# MITAvionicsRevA.net
KiCad netlist of a schematic drawn in EAGLE
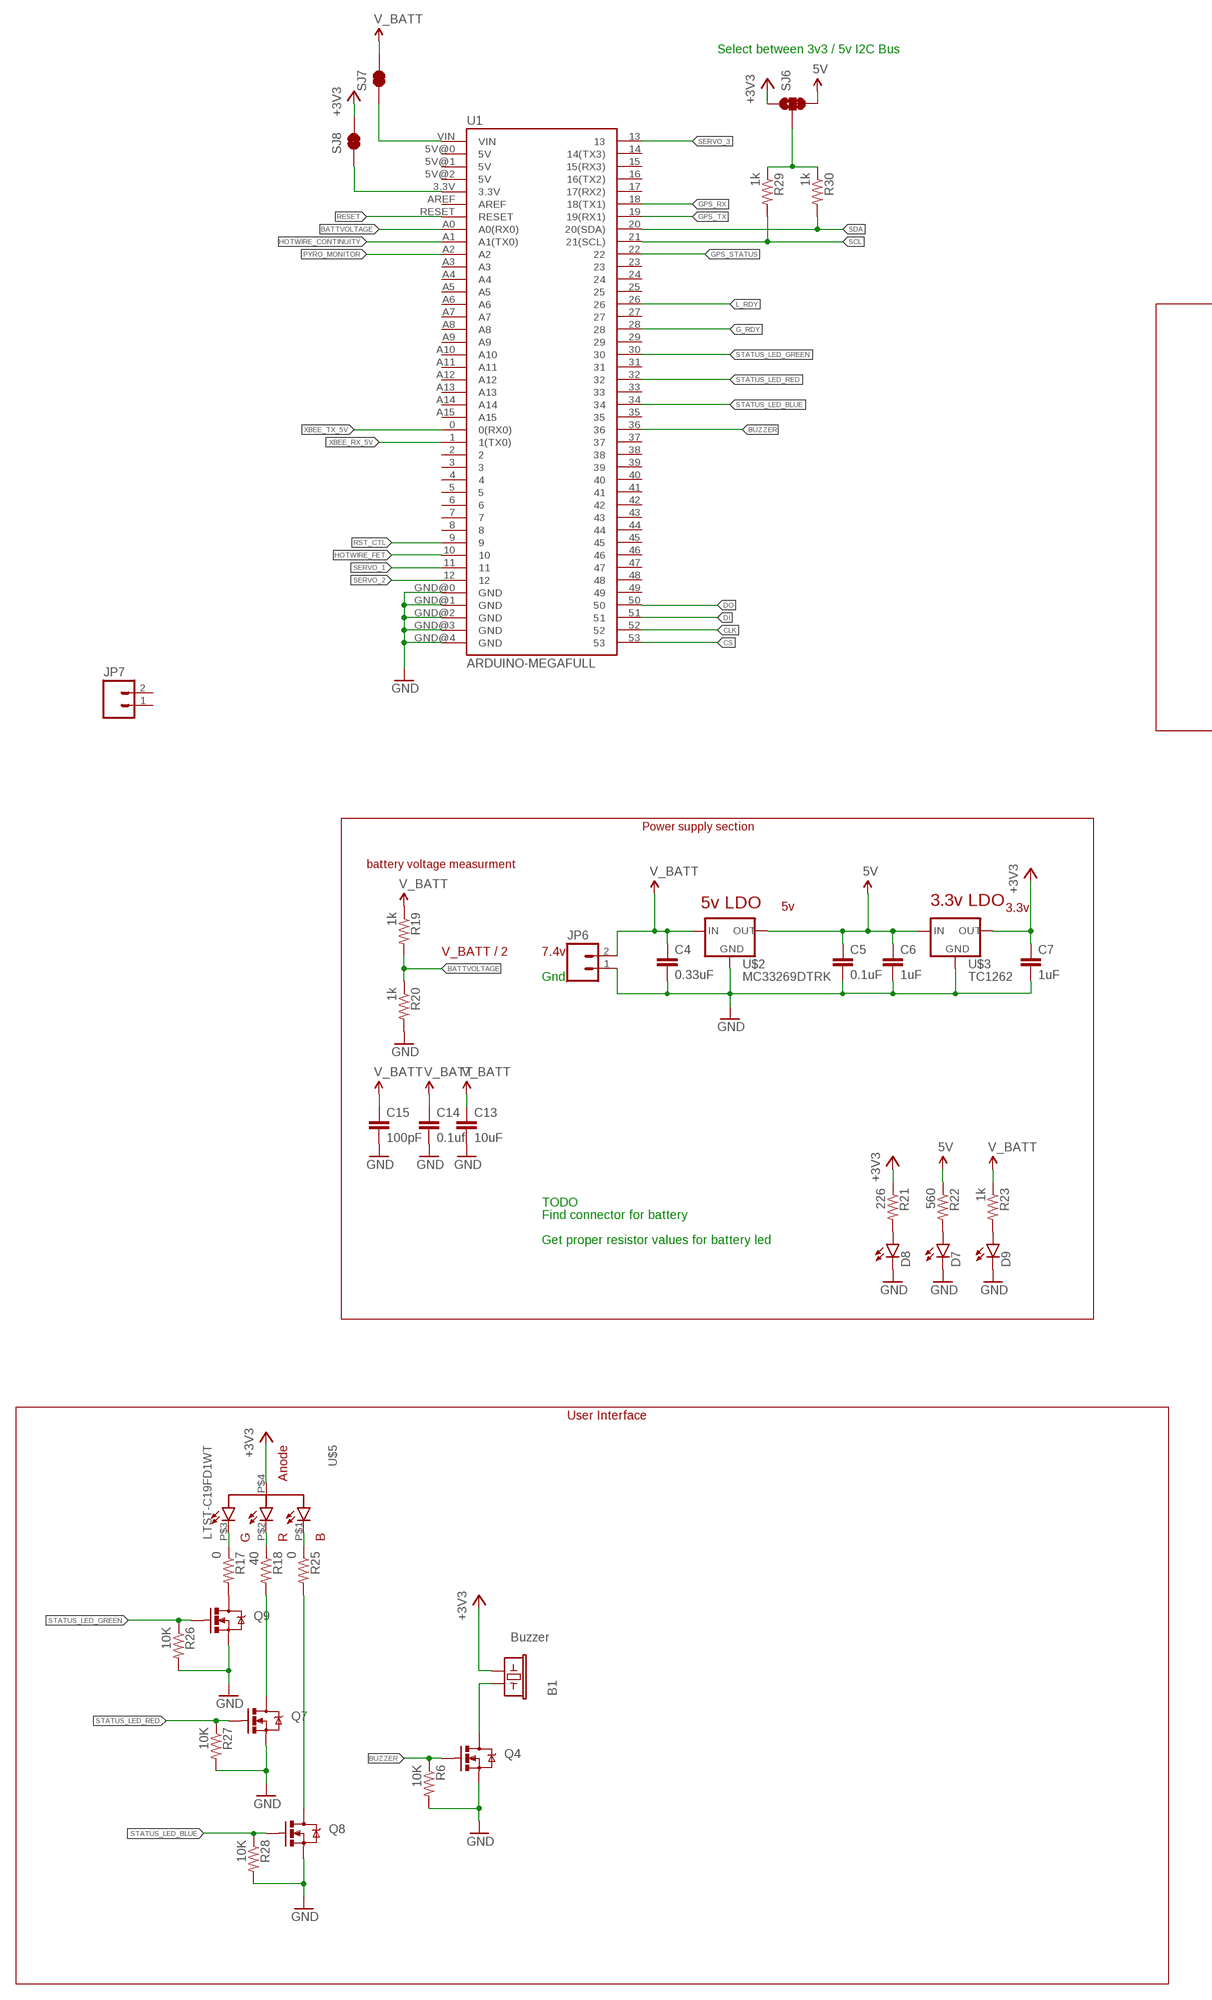
[diagram p0: schematic, sheet 1, part 1 of 2]
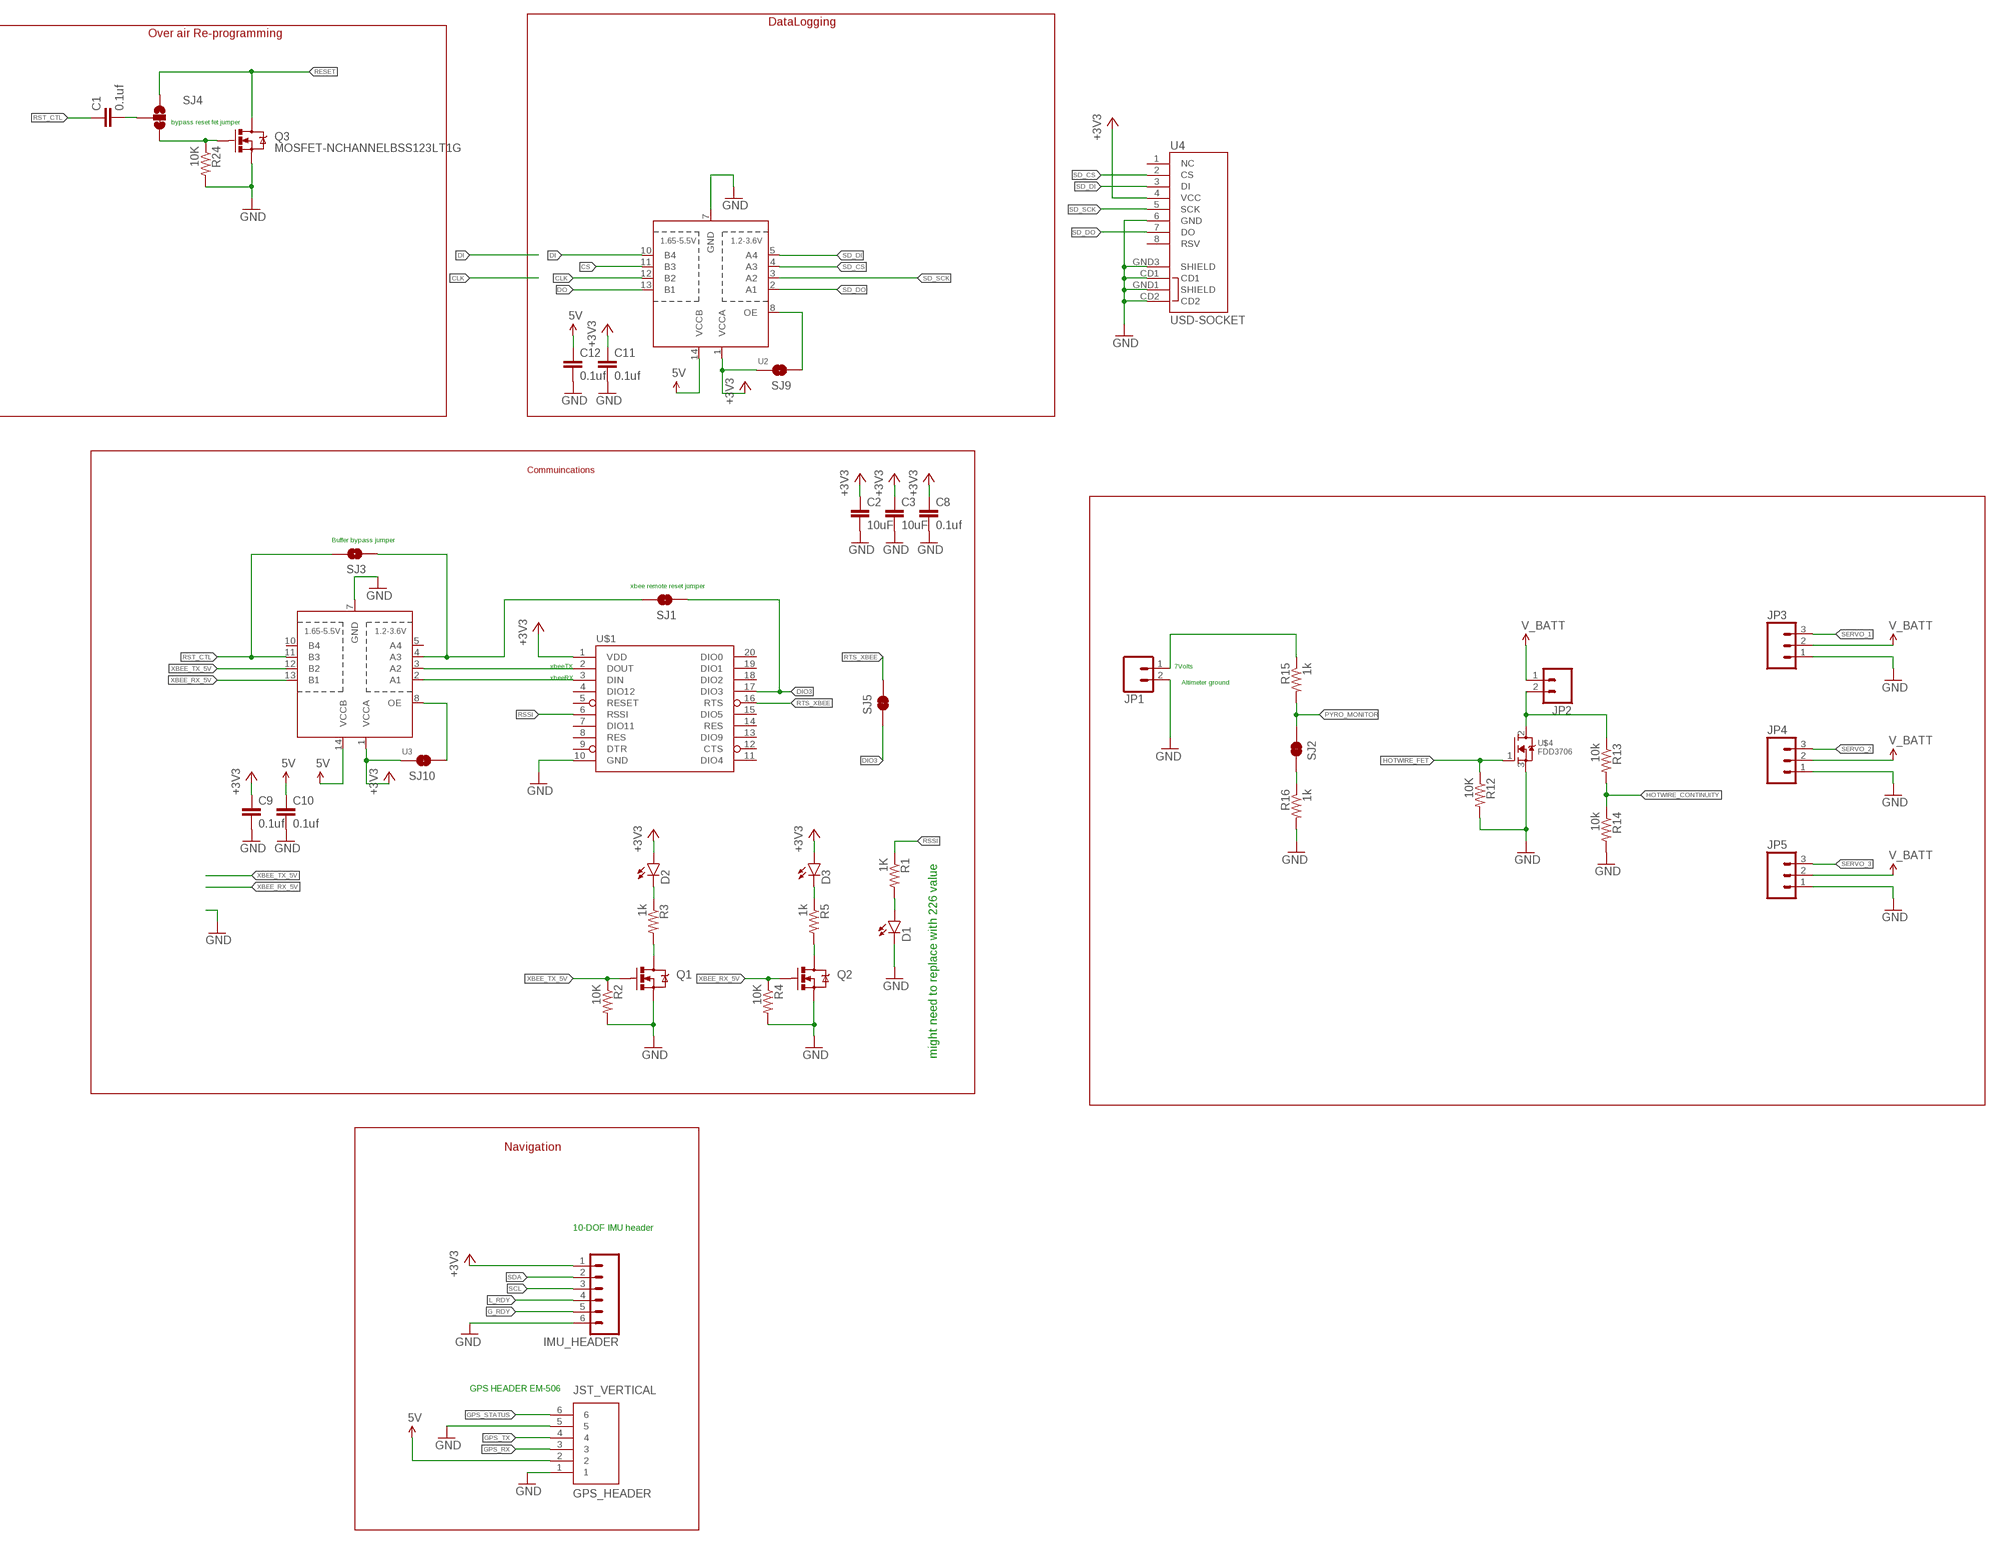
[diagram p1: schematic, sheet 1, part 2 of 2]

(export (version "E")
  (design (tool "Eeschema 10.0.6"))
  (components
    (comp (ref "B1")
      (value "Buzzer")
      (footprint "eagle-import:BUZZER-CCV")
      (libsource (lib "eagle-import") (part "BUZZERSMD2"))
    )
    (comp (ref "C1")
      (value "0.1uf")
      (footprint "eagle-import:0805")
      (libsource (lib "eagle-import") (part "CAP0805"))
    )
    (comp (ref "C2")
      (value "10uF")
      (footprint "eagle-import:0805")
      (libsource (lib "eagle-import") (part "CAP0805"))
    )
    (comp (ref "C3")
      (value "10uF")
      (footprint "eagle-import:0805")
      (libsource (lib "eagle-import") (part "CAP0805"))
    )
    (comp (ref "C4")
      (value "0.33uF")
      (footprint "eagle-import:0805")
      (libsource (lib "eagle-import") (part "CAP0805"))
    )
    (comp (ref "C5")
      (value "0.1uF")
      (footprint "eagle-import:0805")
      (libsource (lib "eagle-import") (part "CAP0805"))
    )
    (comp (ref "C6")
      (value "1uF")
      (footprint "eagle-import:0805")
      (libsource (lib "eagle-import") (part "CAP0805"))
    )
    (comp (ref "C7")
      (value "1uF")
      (footprint "eagle-import:0805")
      (libsource (lib "eagle-import") (part "CAP0805"))
    )
    (comp (ref "C8")
      (value "0.1uf")
      (footprint "eagle-import:0805")
      (libsource (lib "eagle-import") (part "CAP0805"))
    )
    (comp (ref "C9")
      (value "0.1uf")
      (footprint "eagle-import:0805")
      (libsource (lib "eagle-import") (part "CAP0805"))
    )
    (comp (ref "C10")
      (value "0.1uf")
      (footprint "eagle-import:0805")
      (libsource (lib "eagle-import") (part "CAP0805"))
    )
    (comp (ref "C11")
      (value "0.1uf")
      (footprint "eagle-import:0805")
      (libsource (lib "eagle-import") (part "CAP0805"))
    )
    (comp (ref "C12")
      (value "0.1uf")
      (footprint "eagle-import:0805")
      (libsource (lib "eagle-import") (part "CAP0805"))
    )
    (comp (ref "C13")
      (value "10uF")
      (footprint "eagle-import:0805")
      (libsource (lib "eagle-import") (part "CAP0805"))
    )
    (comp (ref "C14")
      (value "0.1uf")
      (footprint "eagle-import:0805")
      (libsource (lib "eagle-import") (part "CAP0805"))
    )
    (comp (ref "C15")
      (value "100pF")
      (footprint "eagle-import:0805")
      (libsource (lib "eagle-import") (part "CAP0805"))
    )
    (comp (ref "D1")
      (value "LED1206")
      (footprint "eagle-import:LED-1206")
      (libsource (lib "eagle-import") (part "LED1206"))
    )
    (comp (ref "D2")
      (value "LED1206")
      (footprint "eagle-import:LED-1206")
      (libsource (lib "eagle-import") (part "LED1206"))
    )
    (comp (ref "D3")
      (value "LED1206")
      (footprint "eagle-import:LED-1206")
      (libsource (lib "eagle-import") (part "LED1206"))
    )
    (comp (ref "D7")
      (value "LED1206")
      (footprint "eagle-import:LED-1206")
      (libsource (lib "eagle-import") (part "LED1206"))
    )
    (comp (ref "D8")
      (value "LED1206")
      (footprint "eagle-import:LED-1206")
      (libsource (lib "eagle-import") (part "LED1206"))
    )
    (comp (ref "D9")
      (value "LED1206")
      (footprint "eagle-import:LED-1206")
      (libsource (lib "eagle-import") (part "LED1206"))
    )
    (comp (ref "GPS_HEADER")
      (value "JST_VERTICAL")
      (footprint "eagle-import:JST-6-SMD-VERT-1.0MM")
      (libsource (lib "eagle-import") (part "JST_VERTICAL"))
    )
    (comp (ref "IMU_HEADER")
      (value "M06SMD-1MM")
      (footprint "eagle-import:1X06-1MM")
      (libsource (lib "eagle-import") (part "M06SMD-1MM"))
    )
    (comp (ref "JP1")
      (value "M023.5MM")
      (footprint "eagle-import:SCREWTERMINAL-3.5MM-2")
      (libsource (lib "eagle-import") (part "M023.5MM"))
    )
    (comp (ref "JP2")
      (value "M023.5MM")
      (footprint "eagle-import:SCREWTERMINAL-3.5MM-2")
      (libsource (lib "eagle-import") (part "M023.5MM"))
    )
    (comp (ref "JP3")
      (value "M03PTH")
      (footprint "eagle-import:1X03")
      (libsource (lib "eagle-import") (part "M03PTH"))
    )
    (comp (ref "JP4")
      (value "M03PTH")
      (footprint "eagle-import:1X03")
      (libsource (lib "eagle-import") (part "M03PTH"))
    )
    (comp (ref "JP5")
      (value "M03PTH")
      (footprint "eagle-import:1X03")
      (libsource (lib "eagle-import") (part "M03PTH"))
    )
    (comp (ref "JP6")
      (value "M023.5MM")
      (footprint "eagle-import:SCREWTERMINAL-3.5MM-2")
      (libsource (lib "eagle-import") (part "M023.5MM"))
    )
    (comp (ref "JP7")
      (value "M02PTH")
      (footprint "eagle-import:1X02")
      (libsource (lib "eagle-import") (part "M02PTH"))
    )
    (comp (ref "Q1")
      (value "MOSFET-NCHANNELBSS123LT1G")
      (footprint "eagle-import:SOT23-3")
      (libsource (lib "eagle-import") (part "MOSFET-NCHANNELBSS123LT1G"))
    )
    (comp (ref "Q2")
      (value "MOSFET-NCHANNELBSS123LT1G")
      (footprint "eagle-import:SOT23-3")
      (libsource (lib "eagle-import") (part "MOSFET-NCHANNELBSS123LT1G"))
    )
    (comp (ref "Q3")
      (value "MOSFET-NCHANNELBSS123LT1G")
      (footprint "eagle-import:SOT23-3")
      (libsource (lib "eagle-import") (part "MOSFET-NCHANNELBSS123LT1G"))
    )
    (comp (ref "Q4")
      (value "MOSFET-NCHANNELBSS123LT1G")
      (footprint "eagle-import:SOT23-3")
      (libsource (lib "eagle-import") (part "MOSFET-NCHANNELBSS123LT1G"))
    )
    (comp (ref "Q7")
      (value "MOSFET-NCHANNELBSS123LT1G")
      (footprint "eagle-import:SOT23-3")
      (libsource (lib "eagle-import") (part "MOSFET-NCHANNELBSS123LT1G"))
    )
    (comp (ref "Q8")
      (value "MOSFET-NCHANNELBSS123LT1G")
      (footprint "eagle-import:SOT23-3")
      (libsource (lib "eagle-import") (part "MOSFET-NCHANNELBSS123LT1G"))
    )
    (comp (ref "Q9")
      (value "MOSFET-NCHANNELBSS123LT1G")
      (footprint "eagle-import:SOT23-3")
      (libsource (lib "eagle-import") (part "MOSFET-NCHANNELBSS123LT1G"))
    )
    (comp (ref "R1")
      (value "1K")
      (footprint "eagle-import:0805")
      (libsource (lib "eagle-import") (part "RESISTOR0805-RES"))
    )
    (comp (ref "R2")
      (value "10K")
      (footprint "eagle-import:0805")
      (libsource (lib "eagle-import") (part "RESISTOR0805-RES"))
    )
    (comp (ref "R3")
      (value "1k")
      (footprint "eagle-import:0805")
      (libsource (lib "eagle-import") (part "RESISTOR0805-RES"))
    )
    (comp (ref "R4")
      (value "10K")
      (footprint "eagle-import:0805")
      (libsource (lib "eagle-import") (part "RESISTOR0805-RES"))
    )
    (comp (ref "R5")
      (value "1k")
      (footprint "eagle-import:0805")
      (libsource (lib "eagle-import") (part "RESISTOR0805-RES"))
    )
    (comp (ref "R6")
      (value "10K")
      (footprint "eagle-import:0805")
      (libsource (lib "eagle-import") (part "RESISTOR0805-RES"))
    )
    (comp (ref "R12")
      (value "10K")
      (footprint "eagle-import:0805")
      (libsource (lib "eagle-import") (part "RESISTOR0805-RES"))
    )
    (comp (ref "R13")
      (value "10k")
      (footprint "eagle-import:0805")
      (libsource (lib "eagle-import") (part "RESISTOR0805-RES"))
    )
    (comp (ref "R14")
      (value "10k")
      (footprint "eagle-import:0805")
      (libsource (lib "eagle-import") (part "RESISTOR0805-RES"))
    )
    (comp (ref "R15")
      (value "1k")
      (footprint "eagle-import:0805")
      (libsource (lib "eagle-import") (part "RESISTOR0805-RES"))
    )
    (comp (ref "R16")
      (value "1k")
      (footprint "eagle-import:0805")
      (libsource (lib "eagle-import") (part "RESISTOR0805-RES"))
    )
    (comp (ref "R17")
      (value "0")
      (footprint "eagle-import:0805")
      (libsource (lib "eagle-import") (part "RESISTOR0805-RES"))
    )
    (comp (ref "R18")
      (value "40")
      (footprint "eagle-import:0805")
      (libsource (lib "eagle-import") (part "RESISTOR0805-RES"))
    )
    (comp (ref "R19")
      (value "1k")
      (footprint "eagle-import:0805")
      (libsource (lib "eagle-import") (part "RESISTOR0805-RES"))
    )
    (comp (ref "R20")
      (value "1k")
      (footprint "eagle-import:0805")
      (libsource (lib "eagle-import") (part "RESISTOR0805-RES"))
    )
    (comp (ref "R21")
      (value "226")
      (footprint "eagle-import:0805")
      (libsource (lib "eagle-import") (part "RESISTOR0805-RES"))
    )
    (comp (ref "R22")
      (value "560")
      (footprint "eagle-import:0805")
      (libsource (lib "eagle-import") (part "RESISTOR0805-RES"))
    )
    (comp (ref "R23")
      (value "1k")
      (footprint "eagle-import:0805")
      (libsource (lib "eagle-import") (part "RESISTOR0805-RES"))
    )
    (comp (ref "R24")
      (value "10K")
      (footprint "eagle-import:0805")
      (libsource (lib "eagle-import") (part "RESISTOR0805-RES"))
    )
    (comp (ref "R25")
      (value "0")
      (footprint "eagle-import:0805")
      (libsource (lib "eagle-import") (part "RESISTOR0805-RES"))
    )
    (comp (ref "R26")
      (value "10K")
      (footprint "eagle-import:0805")
      (libsource (lib "eagle-import") (part "RESISTOR0805-RES"))
    )
    (comp (ref "R27")
      (value "10K")
      (footprint "eagle-import:0805")
      (libsource (lib "eagle-import") (part "RESISTOR0805-RES"))
    )
    (comp (ref "R28")
      (value "10K")
      (footprint "eagle-import:0805")
      (libsource (lib "eagle-import") (part "RESISTOR0805-RES"))
    )
    (comp (ref "R29")
      (value "1k")
      (footprint "eagle-import:0805")
      (libsource (lib "eagle-import") (part "RESISTOR0805-RES"))
    )
    (comp (ref "R30")
      (value "1k")
      (footprint "eagle-import:0805")
      (libsource (lib "eagle-import") (part "RESISTOR0805-RES"))
    )
    (comp (ref "SJ1")
      (value "JUMPER-PAD-2-NC_BY_TRACE")
      (footprint "eagle-import:PAD-JUMPER-2-NC_BY_TRACE_YES_SILK")
      (libsource (lib "eagle-import") (part "JUMPER-PAD-2-NC_BY_TRACE"))
    )
    (comp (ref "SJ2")
      (value "JUMPER-PAD-2-NC_BY_TRACE")
      (footprint "eagle-import:PAD-JUMPER-2-NC_BY_TRACE_YES_SILK")
      (libsource (lib "eagle-import") (part "JUMPER-PAD-2-NC_BY_TRACE"))
    )
    (comp (ref "SJ3")
      (value "JUMPER-PAD-2-NOYES_SILK")
      (footprint "eagle-import:PAD-JUMPER-2-NO_YES_SILK")
      (libsource (lib "eagle-import") (part "JUMPER-PAD-2-NOYES_SILK"))
    )
    (comp (ref "SJ4")
      (value "JUMPER-PAD-3-2OF3_NC_BY_TRACE_SMALL")
      (footprint "eagle-import:PAD-JUMPER-3-2OF3_NC_BY_TRACE_YES_SILK_FULL_BOX")
      (libsource (lib "eagle-import") (part "JUMPER-PAD-3-2OF3_NC_BY_TRACE_SMALL"))
    )
    (comp (ref "SJ5")
      (value "JUMPER-PAD-2-NC_BY_TRACE")
      (footprint "eagle-import:PAD-JUMPER-2-NC_BY_TRACE_YES_SILK")
      (libsource (lib "eagle-import") (part "JUMPER-PAD-2-NC_BY_TRACE"))
    )
    (comp (ref "SJ6")
      (value "JUMPER-PAD-3-2OF3_NC_BY_TRACE_SMALL")
      (footprint "eagle-import:PAD-JUMPER-3-2OF3_NC_BY_TRACE_YES_SILK_FULL_BOX")
      (libsource (lib "eagle-import") (part "JUMPER-PAD-3-2OF3_NC_BY_TRACE_SMALL"))
    )
    (comp (ref "SJ7")
      (value "JUMPER-PAD-2-NC_BY_TRACE")
      (footprint "eagle-import:PAD-JUMPER-2-NC_BY_TRACE_YES_SILK")
      (libsource (lib "eagle-import") (part "JUMPER-PAD-2-NC_BY_TRACE"))
    )
    (comp (ref "SJ8")
      (value "JUMPER-PAD-2-NC_BY_TRACE")
      (footprint "eagle-import:PAD-JUMPER-2-NC_BY_TRACE_YES_SILK")
      (libsource (lib "eagle-import") (part "JUMPER-PAD-2-NC_BY_TRACE"))
    )
    (comp (ref "SJ9")
      (value "JUMPER-PAD-2-NC_BY_TRACE")
      (footprint "eagle-import:PAD-JUMPER-2-NC_BY_TRACE_YES_SILK")
      (libsource (lib "eagle-import") (part "JUMPER-PAD-2-NC_BY_TRACE"))
    )
    (comp (ref "SJ10")
      (value "JUMPER-PAD-2-NC_BY_TRACE")
      (footprint "eagle-import:PAD-JUMPER-2-NC_BY_TRACE_YES_SILK")
      (libsource (lib "eagle-import") (part "JUMPER-PAD-2-NC_BY_TRACE"))
    )
    (comp (ref "U$1")
      (value "XBEE-1B3")
      (footprint "eagle-import:XBEE-SMD")
      (libsource (lib "eagle-import") (part "XBEE-1B3"))
    )
    (comp (ref "U$2")
      (value "MC33269DTRK")
      (footprint "eagle-import:TO-252")
      (libsource (lib "eagle-import") (part "MC33269DTRK"))
    )
    (comp (ref "U$3")
      (value "TC1262")
      (footprint "eagle-import:SOT223")
      (libsource (lib "eagle-import") (part "TC1262"))
    )
    (comp (ref "U$4")
      (value "FDD3706")
      (footprint "eagle-import:TO-252")
      (fields (field (name "DIGIKEY_PART_NUMBER") "FDD3706FSCT-ND"))
      (libsource (lib "eagle-import") (part "FDD3706"))
    )
    (comp (ref "U$5")
      (value "LTST-C19FD1WT")
      (footprint "eagle-import:SMD-4")
      (libsource (lib "eagle-import") (part "LTST-C19FD1WT"))
    )
    (comp (ref "U1")
      (value "ARDUINO-MEGAFULL")
      (footprint "eagle-import:ARDUINO_MEGA")
      (libsource (lib "eagle-import") (part "ARDUINO-MEGAFULL"))
    )
    (comp (ref "U2")
      (value "TXB0104PWRSOIC14")
      (footprint "eagle-import:SO14")
      (libsource (lib "eagle-import") (part "TXB0104PWRSOIC14"))
    )
    (comp (ref "U3")
      (value "TXB0104PWRSOIC14")
      (footprint "eagle-import:SO14")
      (libsource (lib "eagle-import") (part "TXB0104PWRSOIC14"))
    )
    (comp (ref "U4")
      (value "USD-SOCKET")
      (footprint "eagle-import:MICROSD_1_1")
      (libsource (lib "eagle-import") (part "USD-SOCKET"))
    )
  )
  (nets
    (net (code "1") (name "+3V3") (class "Default")
      (node (ref "B1") (pin "-") (pinfunction "2_-") (pintype "passive"))
      (node (ref "C11") (pin "1") (pinfunction "1_1") (pintype "passive"))
      (node (ref "C2") (pin "1") (pinfunction "1_1") (pintype "passive"))
      (node (ref "C3") (pin "1") (pinfunction "1_1") (pintype "passive"))
      (node (ref "C7") (pin "1") (pinfunction "1_1") (pintype "passive"))
      (node (ref "C8") (pin "1") (pinfunction "1_1") (pintype "passive"))
      (node (ref "C9") (pin "1") (pinfunction "1_1") (pintype "passive"))
      (node (ref "D2") (pin "A") (pinfunction "A_A") (pintype "passive"))
      (node (ref "D3") (pin "A") (pinfunction "A_A") (pintype "passive"))
      (node (ref "IMU_HEADER") (pin "1") (pinfunction "1_1") (pintype "passive"))
      (node (ref "R21") (pin "1") (pinfunction "1_1") (pintype "passive"))
      (node (ref "SJ10") (pin "2") (pinfunction "2_2") (pintype "passive"))
      (node (ref "SJ6") (pin "1") (pinfunction "1_1") (pintype "passive"))
      (node (ref "SJ8") (pin "2") (pinfunction "2_2") (pintype "passive"))
      (node (ref "SJ9") (pin "2") (pinfunction "2_2") (pintype "passive"))
      (node (ref "U$1") (pin "1") (pinfunction "VDD_1") (pintype "power_in"))
      (node (ref "U$3") (pin "3") (pinfunction "OUT_3") (pintype "output"))
      (node (ref "U$5") (pin "P$4") (pinfunction "VCC_P$4") (pintype "bidirectional"))
      (node (ref "U2") (pin "1") (pinfunction "VCCA_1") (pintype "bidirectional"))
      (node (ref "U3") (pin "1") (pinfunction "VCCA_1") (pintype "bidirectional"))
      (node (ref "U4") (pin "4") (pinfunction "VCC_4") (pintype "bidirectional"))
    )
    (net (code "2") (name "5V") (class "Default")
      (node (ref "C10") (pin "1") (pinfunction "1_1") (pintype "passive"))
      (node (ref "C12") (pin "1") (pinfunction "1_1") (pintype "passive"))
      (node (ref "C5") (pin "1") (pinfunction "1_1") (pintype "passive"))
      (node (ref "C6") (pin "1") (pinfunction "1_1") (pintype "passive"))
      (node (ref "GPS_HEADER") (pin "2") (pinfunction "2_2") (pintype "bidirectional"))
      (node (ref "R22") (pin "1") (pinfunction "1_1") (pintype "passive"))
      (node (ref "SJ6") (pin "3") (pinfunction "3_3") (pintype "passive"))
      (node (ref "U$2") (pin "2") (pinfunction "OUT_2") (pintype "output"))
      (node (ref "U$3") (pin "1") (pinfunction "IN_1") (pintype "input"))
      (node (ref "U2") (pin "14") (pinfunction "VCCB_14") (pintype "bidirectional"))
      (node (ref "U3") (pin "14") (pinfunction "VCCB_14") (pintype "bidirectional"))
    )
    (net (code "3") (name "BATTVOLTAGE") (class "Default")
      (node (ref "R19") (pin "2") (pinfunction "2_2") (pintype "passive"))
      (node (ref "R20") (pin "1") (pinfunction "1_1") (pintype "passive"))
      (node (ref "U1") (pin "A0") (pinfunction "A0(RX0)_A0") (pintype "bidirectional"))
    )
    (net (code "4") (name "BUZZER") (class "Default")
      (node (ref "Q4") (pin "1") (pinfunction "G_1") (pintype "passive"))
      (node (ref "R6") (pin "1") (pinfunction "1_1") (pintype "passive"))
      (node (ref "U1") (pin "36") (pinfunction "36_36") (pintype "bidirectional"))
    )
    (net (code "5") (name "CLK") (class "Default")
      (node (ref "U1") (pin "52") (pinfunction "52_52") (pintype "bidirectional"))
      (node (ref "U2") (pin "12") (pinfunction "B2_12") (pintype "bidirectional"))
    )
    (net (code "6") (name "CS") (class "Default")
      (node (ref "U1") (pin "53") (pinfunction "53_53") (pintype "bidirectional"))
      (node (ref "U2") (pin "11") (pinfunction "B3_11") (pintype "bidirectional"))
    )
    (net (code "7") (name "DI") (class "Default")
      (node (ref "U1") (pin "51") (pinfunction "51_51") (pintype "bidirectional"))
      (node (ref "U2") (pin "10") (pinfunction "B4_10") (pintype "bidirectional"))
    )
    (net (code "8") (name "DIO3") (class "Default")
      (node (ref "SJ1") (pin "1") (pinfunction "1_1") (pintype "passive"))
      (node (ref "SJ5") (pin "1") (pinfunction "1_1") (pintype "passive"))
      (node (ref "U$1") (pin "17") (pinfunction "DIO3_17") (pintype "bidirectional"))
    )
    (net (code "9") (name "DO") (class "Default")
      (node (ref "U1") (pin "50") (pinfunction "50_50") (pintype "bidirectional"))
      (node (ref "U2") (pin "13") (pinfunction "B1_13") (pintype "bidirectional"))
    )
    (net (code "10") (name "GND") (class "Default")
      (node (ref "C10") (pin "2") (pinfunction "2_2") (pintype "passive"))
      (node (ref "C11") (pin "2") (pinfunction "2_2") (pintype "passive"))
      (node (ref "C12") (pin "2") (pinfunction "2_2") (pintype "passive"))
      (node (ref "C13") (pin "2") (pinfunction "2_2") (pintype "passive"))
      (node (ref "C14") (pin "2") (pinfunction "2_2") (pintype "passive"))
      (node (ref "C15") (pin "2") (pinfunction "2_2") (pintype "passive"))
      (node (ref "C2") (pin "2") (pinfunction "2_2") (pintype "passive"))
      (node (ref "C3") (pin "2") (pinfunction "2_2") (pintype "passive"))
      (node (ref "C4") (pin "2") (pinfunction "2_2") (pintype "passive"))
      (node (ref "C5") (pin "2") (pinfunction "2_2") (pintype "passive"))
      (node (ref "C6") (pin "2") (pinfunction "2_2") (pintype "passive"))
      (node (ref "C7") (pin "2") (pinfunction "2_2") (pintype "passive"))
      (node (ref "C8") (pin "2") (pinfunction "2_2") (pintype "passive"))
      (node (ref "C9") (pin "2") (pinfunction "2_2") (pintype "passive"))
      (node (ref "D1") (pin "C") (pinfunction "C_C") (pintype "passive"))
      (node (ref "D7") (pin "C") (pinfunction "C_C") (pintype "passive"))
      (node (ref "D8") (pin "C") (pinfunction "C_C") (pintype "passive"))
      (node (ref "D9") (pin "C") (pinfunction "C_C") (pintype "passive"))
      (node (ref "GPS_HEADER") (pin "1") (pinfunction "1_1") (pintype "bidirectional"))
      (node (ref "GPS_HEADER") (pin "5") (pinfunction "5_5") (pintype "bidirectional"))
      (node (ref "IMU_HEADER") (pin "6") (pinfunction "6_6") (pintype "passive"))
      (node (ref "JP1") (pin "2") (pinfunction "2_2") (pintype "passive"))
      (node (ref "JP3") (pin "1") (pinfunction "1_1") (pintype "passive"))
      (node (ref "JP4") (pin "1") (pinfunction "1_1") (pintype "passive"))
      (node (ref "JP5") (pin "1") (pinfunction "1_1") (pintype "passive"))
      (node (ref "JP6") (pin "1") (pinfunction "1_1") (pintype "passive"))
      (node (ref "Q1") (pin "2") (pinfunction "S_2") (pintype "passive"))
      (node (ref "Q2") (pin "2") (pinfunction "S_2") (pintype "passive"))
      (node (ref "Q3") (pin "2") (pinfunction "S_2") (pintype "passive"))
      (node (ref "Q4") (pin "2") (pinfunction "S_2") (pintype "passive"))
      (node (ref "Q7") (pin "2") (pinfunction "S_2") (pintype "passive"))
      (node (ref "Q8") (pin "2") (pinfunction "S_2") (pintype "passive"))
      (node (ref "Q9") (pin "2") (pinfunction "S_2") (pintype "passive"))
      (node (ref "R12") (pin "2") (pinfunction "2_2") (pintype "passive"))
      (node (ref "R14") (pin "2") (pinfunction "2_2") (pintype "passive"))
      (node (ref "R16") (pin "2") (pinfunction "2_2") (pintype "passive"))
      (node (ref "R2") (pin "2") (pinfunction "2_2") (pintype "passive"))
      (node (ref "R20") (pin "2") (pinfunction "2_2") (pintype "passive"))
      (node (ref "R24") (pin "2") (pinfunction "2_2") (pintype "passive"))
      (node (ref "R26") (pin "2") (pinfunction "2_2") (pintype "passive"))
      (node (ref "R27") (pin "2") (pinfunction "2_2") (pintype "passive"))
      (node (ref "R28") (pin "2") (pinfunction "2_2") (pintype "passive"))
      (node (ref "R4") (pin "2") (pinfunction "2_2") (pintype "passive"))
      (node (ref "R6") (pin "2") (pinfunction "2_2") (pintype "passive"))
      (node (ref "U$1") (pin "10") (pinfunction "GND_10") (pintype "power_in"))
      (node (ref "U$2") (pin "1") (pinfunction "GND_1") (pintype "input"))
      (node (ref "U$3") (pin "2") (pinfunction "GND_2") (pintype "input"))
      (node (ref "U$4") (pin "3") (pinfunction "S_3") (pintype "bidirectional"))
      (node (ref "U1") (pin "GND@0") (pinfunction "GND_GND@0") (pintype "bidirectional"))
      (node (ref "U1") (pin "GND@1") (pinfunction "GND_GND@1") (pintype "bidirectional"))
      (node (ref "U1") (pin "GND@2") (pinfunction "GND_GND@2") (pintype "bidirectional"))
      (node (ref "U1") (pin "GND@3") (pinfunction "GND_GND@3") (pintype "bidirectional"))
      (node (ref "U1") (pin "GND@4") (pinfunction "GND_GND@4") (pintype "bidirectional"))
      (node (ref "U2") (pin "7") (pinfunction "GND_7") (pintype "bidirectional"))
      (node (ref "U3") (pin "7") (pinfunction "GND_7") (pintype "bidirectional"))
      (node (ref "U4") (pin "6") (pinfunction "GND_6") (pintype "bidirectional"))
      (node (ref "U4") (pin "CD1") (pinfunction "CD1_CD1") (pintype "bidirectional"))
      (node (ref "U4") (pin "CD2") (pinfunction "CD2_CD2") (pintype "bidirectional"))
      (node (ref "U4") (pin "GND1") (pinfunction "SHIELD_GND1") (pintype "bidirectional"))
      (node (ref "U4") (pin "GND3") (pinfunction "SHIELD_GND3") (pintype "bidirectional"))
    )
    (net (code "11") (name "GPS_RX") (class "Default")
      (node (ref "GPS_HEADER") (pin "3") (pinfunction "3_3") (pintype "bidirectional"))
      (node (ref "U1") (pin "18") (pinfunction "18(TX1)_18") (pintype "bidirectional"))
    )
    (net (code "12") (name "GPS_STATUS") (class "Default")
      (node (ref "GPS_HEADER") (pin "6") (pinfunction "6_6") (pintype "bidirectional"))
      (node (ref "U1") (pin "22") (pinfunction "22_22") (pintype "bidirectional"))
    )
    (net (code "13") (name "GPS_TX") (class "Default")
      (node (ref "GPS_HEADER") (pin "4") (pinfunction "4_4") (pintype "bidirectional"))
      (node (ref "U1") (pin "19") (pinfunction "19(RX1)_19") (pintype "bidirectional"))
    )
    (net (code "14") (name "G_RDY") (class "Default")
      (node (ref "IMU_HEADER") (pin "5") (pinfunction "5_5") (pintype "passive"))
      (node (ref "U1") (pin "28") (pinfunction "28_28") (pintype "bidirectional"))
    )
    (net (code "15") (name "HOTWIRE_CONTINUITY") (class "Default")
      (node (ref "R13") (pin "2") (pinfunction "2_2") (pintype "passive"))
      (node (ref "R14") (pin "1") (pinfunction "1_1") (pintype "passive"))
      (node (ref "U1") (pin "A1") (pinfunction "A1(TX0)_A1") (pintype "bidirectional"))
    )
    (net (code "16") (name "HOTWIRE_FET") (class "Default")
      (node (ref "R12") (pin "1") (pinfunction "1_1") (pintype "passive"))
      (node (ref "U$4") (pin "1") (pinfunction "G_1") (pintype "bidirectional"))
      (node (ref "U1") (pin "10") (pinfunction "10_10") (pintype "bidirectional"))
    )
    (net (code "17") (name "L_RDY") (class "Default")
      (node (ref "IMU_HEADER") (pin "4") (pinfunction "4_4") (pintype "passive"))
      (node (ref "U1") (pin "26") (pinfunction "26_26") (pintype "bidirectional"))
    )
    (net (code "18") (name "Net-(B1-1)") (class "Default")
      (node (ref "B1") (pin "+") (pinfunction "1_+") (pintype "passive"))
      (node (ref "Q4") (pin "3") (pinfunction "D_3") (pintype "passive"))
    )
    (net (code "19") (name "Net-(C1-Pad2)") (class "Default")
      (node (ref "C1") (pin "2") (pinfunction "2_2") (pintype "passive"))
      (node (ref "SJ4") (pin "2") (pinfunction "2_2") (pintype "passive"))
    )
    (net (code "20") (name "Net-(D1-PadA)") (class "Default")
      (node (ref "D1") (pin "A") (pinfunction "A_A") (pintype "passive"))
      (node (ref "R1") (pin "2") (pinfunction "2_2") (pintype "passive"))
    )
    (net (code "21") (name "Net-(D2-PadC)") (class "Default")
      (node (ref "D2") (pin "C") (pinfunction "C_C") (pintype "passive"))
      (node (ref "R3") (pin "1") (pinfunction "1_1") (pintype "passive"))
    )
    (net (code "22") (name "Net-(D3-PadC)") (class "Default")
      (node (ref "D3") (pin "C") (pinfunction "C_C") (pintype "passive"))
      (node (ref "R5") (pin "1") (pinfunction "1_1") (pintype "passive"))
    )
    (net (code "23") (name "Net-(D7-PadA)") (class "Default")
      (node (ref "D7") (pin "A") (pinfunction "A_A") (pintype "passive"))
      (node (ref "R22") (pin "2") (pinfunction "2_2") (pintype "passive"))
    )
    (net (code "24") (name "Net-(D8-PadA)") (class "Default")
      (node (ref "D8") (pin "A") (pinfunction "A_A") (pintype "passive"))
      (node (ref "R21") (pin "2") (pinfunction "2_2") (pintype "passive"))
    )
    (net (code "25") (name "Net-(D9-PadA)") (class "Default")
      (node (ref "D9") (pin "A") (pinfunction "A_A") (pintype "passive"))
      (node (ref "R23") (pin "2") (pinfunction "2_2") (pintype "passive"))
    )
    (net (code "26") (name "Net-(JP1-Pad1)") (class "Default")
      (node (ref "JP1") (pin "1") (pinfunction "1_1") (pintype "passive"))
      (node (ref "R15") (pin "1") (pinfunction "1_1") (pintype "passive"))
    )
    (net (code "27") (name "Net-(Q1-D)") (class "Default")
      (node (ref "Q1") (pin "3") (pinfunction "D_3") (pintype "passive"))
      (node (ref "R3") (pin "2") (pinfunction "2_2") (pintype "passive"))
    )
    (net (code "28") (name "Net-(Q2-D)") (class "Default")
      (node (ref "Q2") (pin "3") (pinfunction "D_3") (pintype "passive"))
      (node (ref "R5") (pin "2") (pinfunction "2_2") (pintype "passive"))
    )
    (net (code "29") (name "Net-(Q3-G)") (class "Default")
      (node (ref "Q3") (pin "1") (pinfunction "G_1") (pintype "passive"))
      (node (ref "R24") (pin "1") (pinfunction "1_1") (pintype "passive"))
      (node (ref "SJ4") (pin "3") (pinfunction "3_3") (pintype "passive"))
    )
    (net (code "30") (name "Net-(Q7-D)") (class "Default")
      (node (ref "Q7") (pin "3") (pinfunction "D_3") (pintype "passive"))
      (node (ref "R18") (pin "2") (pinfunction "2_2") (pintype "passive"))
    )
    (net (code "31") (name "Net-(Q8-D)") (class "Default")
      (node (ref "Q8") (pin "3") (pinfunction "D_3") (pintype "passive"))
      (node (ref "R25") (pin "2") (pinfunction "2_2") (pintype "passive"))
    )
    (net (code "32") (name "Net-(Q9-D)") (class "Default")
      (node (ref "Q9") (pin "3") (pinfunction "D_3") (pintype "passive"))
      (node (ref "R17") (pin "2") (pinfunction "2_2") (pintype "passive"))
    )
    (net (code "33") (name "Net-(R16-Pad1)") (class "Default")
      (node (ref "R16") (pin "1") (pinfunction "1_1") (pintype "passive"))
      (node (ref "SJ2") (pin "1") (pinfunction "1_1") (pintype "passive"))
    )
    (net (code "34") (name "Net-(R29-Pad1)") (class "Default")
      (node (ref "R29") (pin "1") (pinfunction "1_1") (pintype "passive"))
      (node (ref "R30") (pin "1") (pinfunction "1_1") (pintype "passive"))
      (node (ref "SJ6") (pin "2") (pinfunction "2_2") (pintype "passive"))
    )
    (net (code "35") (name "Net-(SJ7-Pad1)") (class "Default")
      (node (ref "SJ7") (pin "1") (pinfunction "1_1") (pintype "passive"))
      (node (ref "U1") (pin "VIN") (pinfunction "VIN_VIN") (pintype "bidirectional"))
    )
    (net (code "36") (name "Net-(SJ8-Pad1)") (class "Default")
      (node (ref "SJ8") (pin "1") (pinfunction "1_1") (pintype "passive"))
      (node (ref "U1") (pin "3.3V") (pinfunction "3.3V_3.3V") (pintype "bidirectional"))
    )
    (net (code "37") (name "Net-(U$1-DIN)") (class "Default")
      (node (ref "U$1") (pin "3") (pinfunction "DIN_3") (pintype "input"))
      (node (ref "U3") (pin "2") (pinfunction "A1_2") (pintype "bidirectional"))
    )
    (net (code "38") (name "Net-(U$1-DOUT)") (class "Default")
      (node (ref "U$1") (pin "2") (pinfunction "DOUT_2") (pintype "output"))
      (node (ref "U3") (pin "3") (pinfunction "A2_3") (pintype "bidirectional"))
    )
    (net (code "39") (name "Net-(U$4-D)") (class "Default")
      (node (ref "JP2") (pin "2") (pinfunction "2_2") (pintype "passive"))
      (node (ref "R13") (pin "1") (pinfunction "1_1") (pintype "passive"))
      (node (ref "U$4") (pin "2") (pinfunction "D_2") (pintype "bidirectional"))
    )
    (net (code "40") (name "Net-(U$5-BLUE)") (class "Default")
      (node (ref "R25") (pin "1") (pinfunction "1_1") (pintype "passive"))
      (node (ref "U$5") (pin "P$1") (pinfunction "BLUE_P$1") (pintype "bidirectional"))
    )
    (net (code "41") (name "Net-(U$5-GREEN)") (class "Default")
      (node (ref "R17") (pin "1") (pinfunction "1_1") (pintype "passive"))
      (node (ref "U$5") (pin "P$3") (pinfunction "GREEN_P$3") (pintype "bidirectional"))
    )
    (net (code "42") (name "Net-(U$5-RED)") (class "Default")
      (node (ref "R18") (pin "1") (pinfunction "1_1") (pintype "passive"))
      (node (ref "U$5") (pin "P$2") (pinfunction "RED_P$2") (pintype "bidirectional"))
    )
    (net (code "43") (name "Net-(U2-OE)") (class "Default")
      (node (ref "SJ9") (pin "1") (pinfunction "1_1") (pintype "passive"))
      (node (ref "U2") (pin "8") (pinfunction "OE_8") (pintype "bidirectional"))
    )
    (net (code "44") (name "Net-(U3-A3)") (class "Default")
      (node (ref "SJ1") (pin "2") (pinfunction "2_2") (pintype "passive"))
      (node (ref "SJ3") (pin "1") (pinfunction "1_1") (pintype "passive"))
      (node (ref "U3") (pin "4") (pinfunction "A3_4") (pintype "bidirectional"))
    )
    (net (code "45") (name "Net-(U3-OE)") (class "Default")
      (node (ref "SJ10") (pin "1") (pinfunction "1_1") (pintype "passive"))
      (node (ref "U3") (pin "8") (pinfunction "OE_8") (pintype "bidirectional"))
    )
    (net (code "46") (name "PYRO_MONITOR") (class "Default")
      (node (ref "R15") (pin "2") (pinfunction "2_2") (pintype "passive"))
      (node (ref "SJ2") (pin "2") (pinfunction "2_2") (pintype "passive"))
      (node (ref "U1") (pin "A2") (pinfunction "A2_A2") (pintype "bidirectional"))
    )
    (net (code "47") (name "RESET") (class "Default")
      (node (ref "Q3") (pin "3") (pinfunction "D_3") (pintype "passive"))
      (node (ref "SJ4") (pin "1") (pinfunction "1_1") (pintype "passive"))
      (node (ref "U1") (pin "RESET") (pinfunction "RESET_RESET") (pintype "bidirectional"))
    )
    (net (code "48") (name "RSSI") (class "Default")
      (node (ref "R1") (pin "1") (pinfunction "1_1") (pintype "passive"))
      (node (ref "U$1") (pin "6") (pinfunction "RSSI_6") (pintype "bidirectional"))
    )
    (net (code "49") (name "RST_CTL") (class "Default")
      (node (ref "C1") (pin "1") (pinfunction "1_1") (pintype "passive"))
      (node (ref "SJ3") (pin "2") (pinfunction "2_2") (pintype "passive"))
      (node (ref "U1") (pin "9") (pinfunction "9_9") (pintype "bidirectional"))
      (node (ref "U3") (pin "11") (pinfunction "B3_11") (pintype "bidirectional"))
    )
    (net (code "50") (name "RTS_XBEE") (class "Default")
      (node (ref "SJ5") (pin "2") (pinfunction "2_2") (pintype "passive"))
      (node (ref "U$1") (pin "16") (pinfunction "RTS_16") (pintype "input"))
    )
    (net (code "51") (name "SCL") (class "Default")
      (node (ref "IMU_HEADER") (pin "3") (pinfunction "3_3") (pintype "passive"))
      (node (ref "R29") (pin "2") (pinfunction "2_2") (pintype "passive"))
      (node (ref "U1") (pin "21") (pinfunction "21(SCL)_21") (pintype "bidirectional"))
    )
    (net (code "52") (name "SDA") (class "Default")
      (node (ref "IMU_HEADER") (pin "2") (pinfunction "2_2") (pintype "passive"))
      (node (ref "R30") (pin "2") (pinfunction "2_2") (pintype "passive"))
      (node (ref "U1") (pin "20") (pinfunction "20(SDA)_20") (pintype "bidirectional"))
    )
    (net (code "53") (name "SD_CS") (class "Default")
      (node (ref "U2") (pin "4") (pinfunction "A3_4") (pintype "bidirectional"))
      (node (ref "U4") (pin "2") (pinfunction "CS_2") (pintype "bidirectional"))
    )
    (net (code "54") (name "SD_DI") (class "Default")
      (node (ref "U2") (pin "5") (pinfunction "A4_5") (pintype "bidirectional"))
      (node (ref "U4") (pin "3") (pinfunction "DI_3") (pintype "bidirectional"))
    )
    (net (code "55") (name "SD_DO") (class "Default")
      (node (ref "U2") (pin "2") (pinfunction "A1_2") (pintype "bidirectional"))
      (node (ref "U4") (pin "7") (pinfunction "DO_7") (pintype "bidirectional"))
    )
    (net (code "56") (name "SD_SCK") (class "Default")
      (node (ref "U2") (pin "3") (pinfunction "A2_3") (pintype "bidirectional"))
      (node (ref "U4") (pin "5") (pinfunction "SCK_5") (pintype "bidirectional"))
    )
    (net (code "57") (name "SERVO_1") (class "Default")
      (node (ref "JP3") (pin "3") (pinfunction "3_3") (pintype "passive"))
      (node (ref "U1") (pin "11") (pinfunction "11_11") (pintype "bidirectional"))
    )
    (net (code "58") (name "SERVO_2") (class "Default")
      (node (ref "JP4") (pin "3") (pinfunction "3_3") (pintype "passive"))
      (node (ref "U1") (pin "12") (pinfunction "12_12") (pintype "bidirectional"))
    )
    (net (code "59") (name "SERVO_3") (class "Default")
      (node (ref "JP5") (pin "3") (pinfunction "3_3") (pintype "passive"))
      (node (ref "U1") (pin "13") (pinfunction "13_13") (pintype "bidirectional"))
    )
    (net (code "60") (name "STATUS_LED_BLUE") (class "Default")
      (node (ref "Q8") (pin "1") (pinfunction "G_1") (pintype "passive"))
      (node (ref "R28") (pin "1") (pinfunction "1_1") (pintype "passive"))
      (node (ref "U1") (pin "34") (pinfunction "34_34") (pintype "bidirectional"))
    )
    (net (code "61") (name "STATUS_LED_GREEN") (class "Default")
      (node (ref "Q9") (pin "1") (pinfunction "G_1") (pintype "passive"))
      (node (ref "R26") (pin "1") (pinfunction "1_1") (pintype "passive"))
      (node (ref "U1") (pin "30") (pinfunction "30_30") (pintype "bidirectional"))
    )
    (net (code "62") (name "STATUS_LED_RED") (class "Default")
      (node (ref "Q7") (pin "1") (pinfunction "G_1") (pintype "passive"))
      (node (ref "R27") (pin "1") (pinfunction "1_1") (pintype "passive"))
      (node (ref "U1") (pin "32") (pinfunction "32_32") (pintype "bidirectional"))
    )
    (net (code "63") (name "V_BATT") (class "Default")
      (node (ref "C13") (pin "1") (pinfunction "1_1") (pintype "passive"))
      (node (ref "C14") (pin "1") (pinfunction "1_1") (pintype "passive"))
      (node (ref "C15") (pin "1") (pinfunction "1_1") (pintype "passive"))
      (node (ref "C4") (pin "1") (pinfunction "1_1") (pintype "passive"))
      (node (ref "JP2") (pin "1") (pinfunction "1_1") (pintype "passive"))
      (node (ref "JP3") (pin "2") (pinfunction "2_2") (pintype "passive"))
      (node (ref "JP4") (pin "2") (pinfunction "2_2") (pintype "passive"))
      (node (ref "JP5") (pin "2") (pinfunction "2_2") (pintype "passive"))
      (node (ref "JP6") (pin "2") (pinfunction "2_2") (pintype "passive"))
      (node (ref "R19") (pin "1") (pinfunction "1_1") (pintype "passive"))
      (node (ref "R23") (pin "1") (pinfunction "1_1") (pintype "passive"))
      (node (ref "SJ7") (pin "2") (pinfunction "2_2") (pintype "passive"))
      (node (ref "U$2") (pin "3") (pinfunction "IN_3") (pintype "input"))
    )
    (net (code "64") (name "XBEE_RX_5V") (class "Default")
      (node (ref "Q2") (pin "1") (pinfunction "G_1") (pintype "passive"))
      (node (ref "R4") (pin "1") (pinfunction "1_1") (pintype "passive"))
      (node (ref "U1") (pin "1") (pinfunction "1(TX0)_1") (pintype "bidirectional"))
      (node (ref "U3") (pin "13") (pinfunction "B1_13") (pintype "bidirectional"))
    )
    (net (code "65") (name "XBEE_TX_5V") (class "Default")
      (node (ref "Q1") (pin "1") (pinfunction "G_1") (pintype "passive"))
      (node (ref "R2") (pin "1") (pinfunction "1_1") (pintype "passive"))
      (node (ref "U1") (pin "0") (pinfunction "0(RX0)_0") (pintype "bidirectional"))
      (node (ref "U3") (pin "12") (pinfunction "B2_12") (pintype "bidirectional"))
    )
    (net (code "66") (name "unconnected-(JP7-Pad1)") (class "Default")
      (node (ref "JP7") (pin "1") (pinfunction "1_1") (pintype "passive"))
    )
    (net (code "67") (name "unconnected-(JP7-Pad2)") (class "Default")
      (node (ref "JP7") (pin "2") (pinfunction "2_2") (pintype "passive"))
    )
    (net (code "68") (name "unconnected-(U$1-CTS-Pad12)") (class "Default")
      (node (ref "U$1") (pin "12") (pinfunction "CTS_12") (pintype "output"))
    )
    (net (code "69") (name "unconnected-(U$1-DIO0-Pad20)") (class "Default")
      (node (ref "U$1") (pin "20") (pinfunction "DIO0_20") (pintype "bidirectional"))
    )
    (net (code "70") (name "unconnected-(U$1-DIO1-Pad19)") (class "Default")
      (node (ref "U$1") (pin "19") (pinfunction "DIO1_19") (pintype "bidirectional"))
    )
    (net (code "71") (name "unconnected-(U$1-DIO2-Pad18)") (class "Default")
      (node (ref "U$1") (pin "18") (pinfunction "DIO2_18") (pintype "bidirectional"))
    )
    (net (code "72") (name "unconnected-(U$1-DIO4-Pad11)") (class "Default")
      (node (ref "U$1") (pin "11") (pinfunction "DIO4_11") (pintype "bidirectional"))
    )
    (net (code "73") (name "unconnected-(U$1-DIO5-Pad15)") (class "Default")
      (node (ref "U$1") (pin "15") (pinfunction "DIO5_15") (pintype "bidirectional"))
    )
    (net (code "74") (name "unconnected-(U$1-DIO9-Pad13)") (class "Default")
      (node (ref "U$1") (pin "13") (pinfunction "DIO9_13") (pintype "bidirectional"))
    )
    (net (code "75") (name "unconnected-(U$1-DIO11-Pad7)") (class "Default")
      (node (ref "U$1") (pin "7") (pinfunction "DIO11_7") (pintype "bidirectional"))
    )
    (net (code "76") (name "unconnected-(U$1-DIO12-Pad4)") (class "Default")
      (node (ref "U$1") (pin "4") (pinfunction "DIO12_4") (pintype "bidirectional"))
    )
    (net (code "77") (name "unconnected-(U$1-DTR-Pad9)") (class "Default")
      (node (ref "U$1") (pin "9") (pinfunction "DTR_9") (pintype "bidirectional"))
    )
    (net (code "78") (name "unconnected-(U$1-RES-Pad8)") (class "Default")
      (node (ref "U$1") (pin "8") (pinfunction "RES_8") (pintype "bidirectional"))
    )
    (net (code "79") (name "unconnected-(U$1-RES-Pad14)") (class "Default")
      (node (ref "U$1") (pin "14") (pinfunction "RES_14") (pintype "bidirectional"))
    )
    (net (code "80") (name "unconnected-(U$1-RESET-Pad5)") (class "Default")
      (node (ref "U$1") (pin "5") (pinfunction "RESET_5") (pintype "input"))
    )
    (net (code "81") (name "unconnected-(U1-5V-Pad5V@0)") (class "Default")
      (node (ref "U1") (pin "5V@0") (pinfunction "5V_5V@0") (pintype "bidirectional"))
    )
    (net (code "82") (name "unconnected-(U1-5V-Pad5V@1)") (class "Default")
      (node (ref "U1") (pin "5V@1") (pinfunction "5V_5V@1") (pintype "bidirectional"))
    )
    (net (code "83") (name "unconnected-(U1-5V-Pad5V@2)") (class "Default")
      (node (ref "U1") (pin "5V@2") (pinfunction "5V_5V@2") (pintype "bidirectional"))
    )
    (net (code "84") (name "unconnected-(U1-14(TX3)-Pad14)") (class "Default")
      (node (ref "U1") (pin "14") (pinfunction "14(TX3)_14") (pintype "bidirectional"))
    )
    (net (code "85") (name "unconnected-(U1-15(RX3)-Pad15)") (class "Default")
      (node (ref "U1") (pin "15") (pinfunction "15(RX3)_15") (pintype "bidirectional"))
    )
    (net (code "86") (name "unconnected-(U1-16(TX2)-Pad16)") (class "Default")
      (node (ref "U1") (pin "16") (pinfunction "16(TX2)_16") (pintype "bidirectional"))
    )
    (net (code "87") (name "unconnected-(U1-17(RX2)-Pad17)") (class "Default")
      (node (ref "U1") (pin "17") (pinfunction "17(RX2)_17") (pintype "bidirectional"))
    )
    (net (code "88") (name "unconnected-(U1-Pad2)") (class "Default")
      (node (ref "U1") (pin "2") (pinfunction "2_2") (pintype "bidirectional"))
    )
    (net (code "89") (name "unconnected-(U1-Pad3)") (class "Default")
      (node (ref "U1") (pin "3") (pinfunction "3_3") (pintype "bidirectional"))
    )
    (net (code "90") (name "unconnected-(U1-Pad4)") (class "Default")
      (node (ref "U1") (pin "4") (pinfunction "4_4") (pintype "bidirectional"))
    )
    (net (code "91") (name "unconnected-(U1-Pad5)") (class "Default")
      (node (ref "U1") (pin "5") (pinfunction "5_5") (pintype "bidirectional"))
    )
    (net (code "92") (name "unconnected-(U1-Pad6)") (class "Default")
      (node (ref "U1") (pin "6") (pinfunction "6_6") (pintype "bidirectional"))
    )
    (net (code "93") (name "unconnected-(U1-Pad7)") (class "Default")
      (node (ref "U1") (pin "7") (pinfunction "7_7") (pintype "bidirectional"))
    )
    (net (code "94") (name "unconnected-(U1-Pad8)") (class "Default")
      (node (ref "U1") (pin "8") (pinfunction "8_8") (pintype "bidirectional"))
    )
    (net (code "95") (name "unconnected-(U1-Pad23)") (class "Default")
      (node (ref "U1") (pin "23") (pinfunction "23_23") (pintype "bidirectional"))
    )
    (net (code "96") (name "unconnected-(U1-Pad24)") (class "Default")
      (node (ref "U1") (pin "24") (pinfunction "24_24") (pintype "bidirectional"))
    )
    (net (code "97") (name "unconnected-(U1-Pad25)") (class "Default")
      (node (ref "U1") (pin "25") (pinfunction "25_25") (pintype "bidirectional"))
    )
    (net (code "98") (name "unconnected-(U1-Pad27)") (class "Default")
      (node (ref "U1") (pin "27") (pinfunction "27_27") (pintype "bidirectional"))
    )
    (net (code "99") (name "unconnected-(U1-Pad29)") (class "Default")
      (node (ref "U1") (pin "29") (pinfunction "29_29") (pintype "bidirectional"))
    )
    (net (code "100") (name "unconnected-(U1-Pad31)") (class "Default")
      (node (ref "U1") (pin "31") (pinfunction "31_31") (pintype "bidirectional"))
    )
    (net (code "101") (name "unconnected-(U1-Pad33)") (class "Default")
      (node (ref "U1") (pin "33") (pinfunction "33_33") (pintype "bidirectional"))
    )
    (net (code "102") (name "unconnected-(U1-Pad35)") (class "Default")
      (node (ref "U1") (pin "35") (pinfunction "35_35") (pintype "bidirectional"))
    )
    (net (code "103") (name "unconnected-(U1-Pad37)") (class "Default")
      (node (ref "U1") (pin "37") (pinfunction "37_37") (pintype "bidirectional"))
    )
    (net (code "104") (name "unconnected-(U1-Pad38)") (class "Default")
      (node (ref "U1") (pin "38") (pinfunction "38_38") (pintype "bidirectional"))
    )
    (net (code "105") (name "unconnected-(U1-Pad39)") (class "Default")
      (node (ref "U1") (pin "39") (pinfunction "39_39") (pintype "bidirectional"))
    )
    (net (code "106") (name "unconnected-(U1-Pad40)") (class "Default")
      (node (ref "U1") (pin "40") (pinfunction "40_40") (pintype "bidirectional"))
    )
    (net (code "107") (name "unconnected-(U1-Pad41)") (class "Default")
      (node (ref "U1") (pin "41") (pinfunction "41_41") (pintype "bidirectional"))
    )
    (net (code "108") (name "unconnected-(U1-Pad42)") (class "Default")
      (node (ref "U1") (pin "42") (pinfunction "42_42") (pintype "bidirectional"))
    )
    (net (code "109") (name "unconnected-(U1-Pad43)") (class "Default")
      (node (ref "U1") (pin "43") (pinfunction "43_43") (pintype "bidirectional"))
    )
    (net (code "110") (name "unconnected-(U1-Pad44)") (class "Default")
      (node (ref "U1") (pin "44") (pinfunction "44_44") (pintype "bidirectional"))
    )
    (net (code "111") (name "unconnected-(U1-Pad45)") (class "Default")
      (node (ref "U1") (pin "45") (pinfunction "45_45") (pintype "bidirectional"))
    )
    (net (code "112") (name "unconnected-(U1-Pad46)") (class "Default")
      (node (ref "U1") (pin "46") (pinfunction "46_46") (pintype "bidirectional"))
    )
    (net (code "113") (name "unconnected-(U1-Pad47)") (class "Default")
      (node (ref "U1") (pin "47") (pinfunction "47_47") (pintype "bidirectional"))
    )
    (net (code "114") (name "unconnected-(U1-Pad48)") (class "Default")
      (node (ref "U1") (pin "48") (pinfunction "48_48") (pintype "bidirectional"))
    )
    (net (code "115") (name "unconnected-(U1-Pad49)") (class "Default")
      (node (ref "U1") (pin "49") (pinfunction "49_49") (pintype "bidirectional"))
    )
    (net (code "116") (name "unconnected-(U1-PadA3)") (class "Default")
      (node (ref "U1") (pin "A3") (pinfunction "A3_A3") (pintype "bidirectional"))
    )
    (net (code "117") (name "unconnected-(U1-PadA4)") (class "Default")
      (node (ref "U1") (pin "A4") (pinfunction "A4_A4") (pintype "bidirectional"))
    )
    (net (code "118") (name "unconnected-(U1-PadA5)") (class "Default")
      (node (ref "U1") (pin "A5") (pinfunction "A5_A5") (pintype "bidirectional"))
    )
    (net (code "119") (name "unconnected-(U1-PadA6)") (class "Default")
      (node (ref "U1") (pin "A6") (pinfunction "A6_A6") (pintype "bidirectional"))
    )
    (net (code "120") (name "unconnected-(U1-PadA7)") (class "Default")
      (node (ref "U1") (pin "A7") (pinfunction "A7_A7") (pintype "bidirectional"))
    )
    (net (code "121") (name "unconnected-(U1-PadA8)") (class "Default")
      (node (ref "U1") (pin "A8") (pinfunction "A8_A8") (pintype "bidirectional"))
    )
    (net (code "122") (name "unconnected-(U1-PadA9)") (class "Default")
      (node (ref "U1") (pin "A9") (pinfunction "A9_A9") (pintype "bidirectional"))
    )
    (net (code "123") (name "unconnected-(U1-PadA10)") (class "Default")
      (node (ref "U1") (pin "A10") (pinfunction "A10_A10") (pintype "bidirectional"))
    )
    (net (code "124") (name "unconnected-(U1-PadA11)") (class "Default")
      (node (ref "U1") (pin "A11") (pinfunction "A11_A11") (pintype "bidirectional"))
    )
    (net (code "125") (name "unconnected-(U1-PadA12)") (class "Default")
      (node (ref "U1") (pin "A12") (pinfunction "A12_A12") (pintype "bidirectional"))
    )
    (net (code "126") (name "unconnected-(U1-PadA13)") (class "Default")
      (node (ref "U1") (pin "A13") (pinfunction "A13_A13") (pintype "bidirectional"))
    )
    (net (code "127") (name "unconnected-(U1-PadA14)") (class "Default")
      (node (ref "U1") (pin "A14") (pinfunction "A14_A14") (pintype "bidirectional"))
    )
    (net (code "128") (name "unconnected-(U1-PadA15)") (class "Default")
      (node (ref "U1") (pin "A15") (pinfunction "A15_A15") (pintype "bidirectional"))
    )
    (net (code "129") (name "unconnected-(U1-PadAREF)") (class "Default")
      (node (ref "U1") (pin "AREF") (pinfunction "AREF_AREF") (pintype "bidirectional"))
    )
    (net (code "130") (name "unconnected-(U3-A4-Pad5)") (class "Default")
      (node (ref "U3") (pin "5") (pinfunction "A4_5") (pintype "bidirectional"))
    )
    (net (code "131") (name "unconnected-(U3-B4-Pad10)") (class "Default")
      (node (ref "U3") (pin "10") (pinfunction "B4_10") (pintype "bidirectional"))
    )
    (net (code "132") (name "unconnected-(U4-NC-Pad1)") (class "Default")
      (node (ref "U4") (pin "1") (pinfunction "NC_1") (pintype "bidirectional"))
    )
    (net (code "133") (name "unconnected-(U4-RSV-Pad8)") (class "Default")
      (node (ref "U4") (pin "8") (pinfunction "RSV_8") (pintype "bidirectional"))
    )
  )
)
